# Pixracer_V1_FMU_Alternative_4.net
KiCad netlist of a schematic drawn in Altium Designer
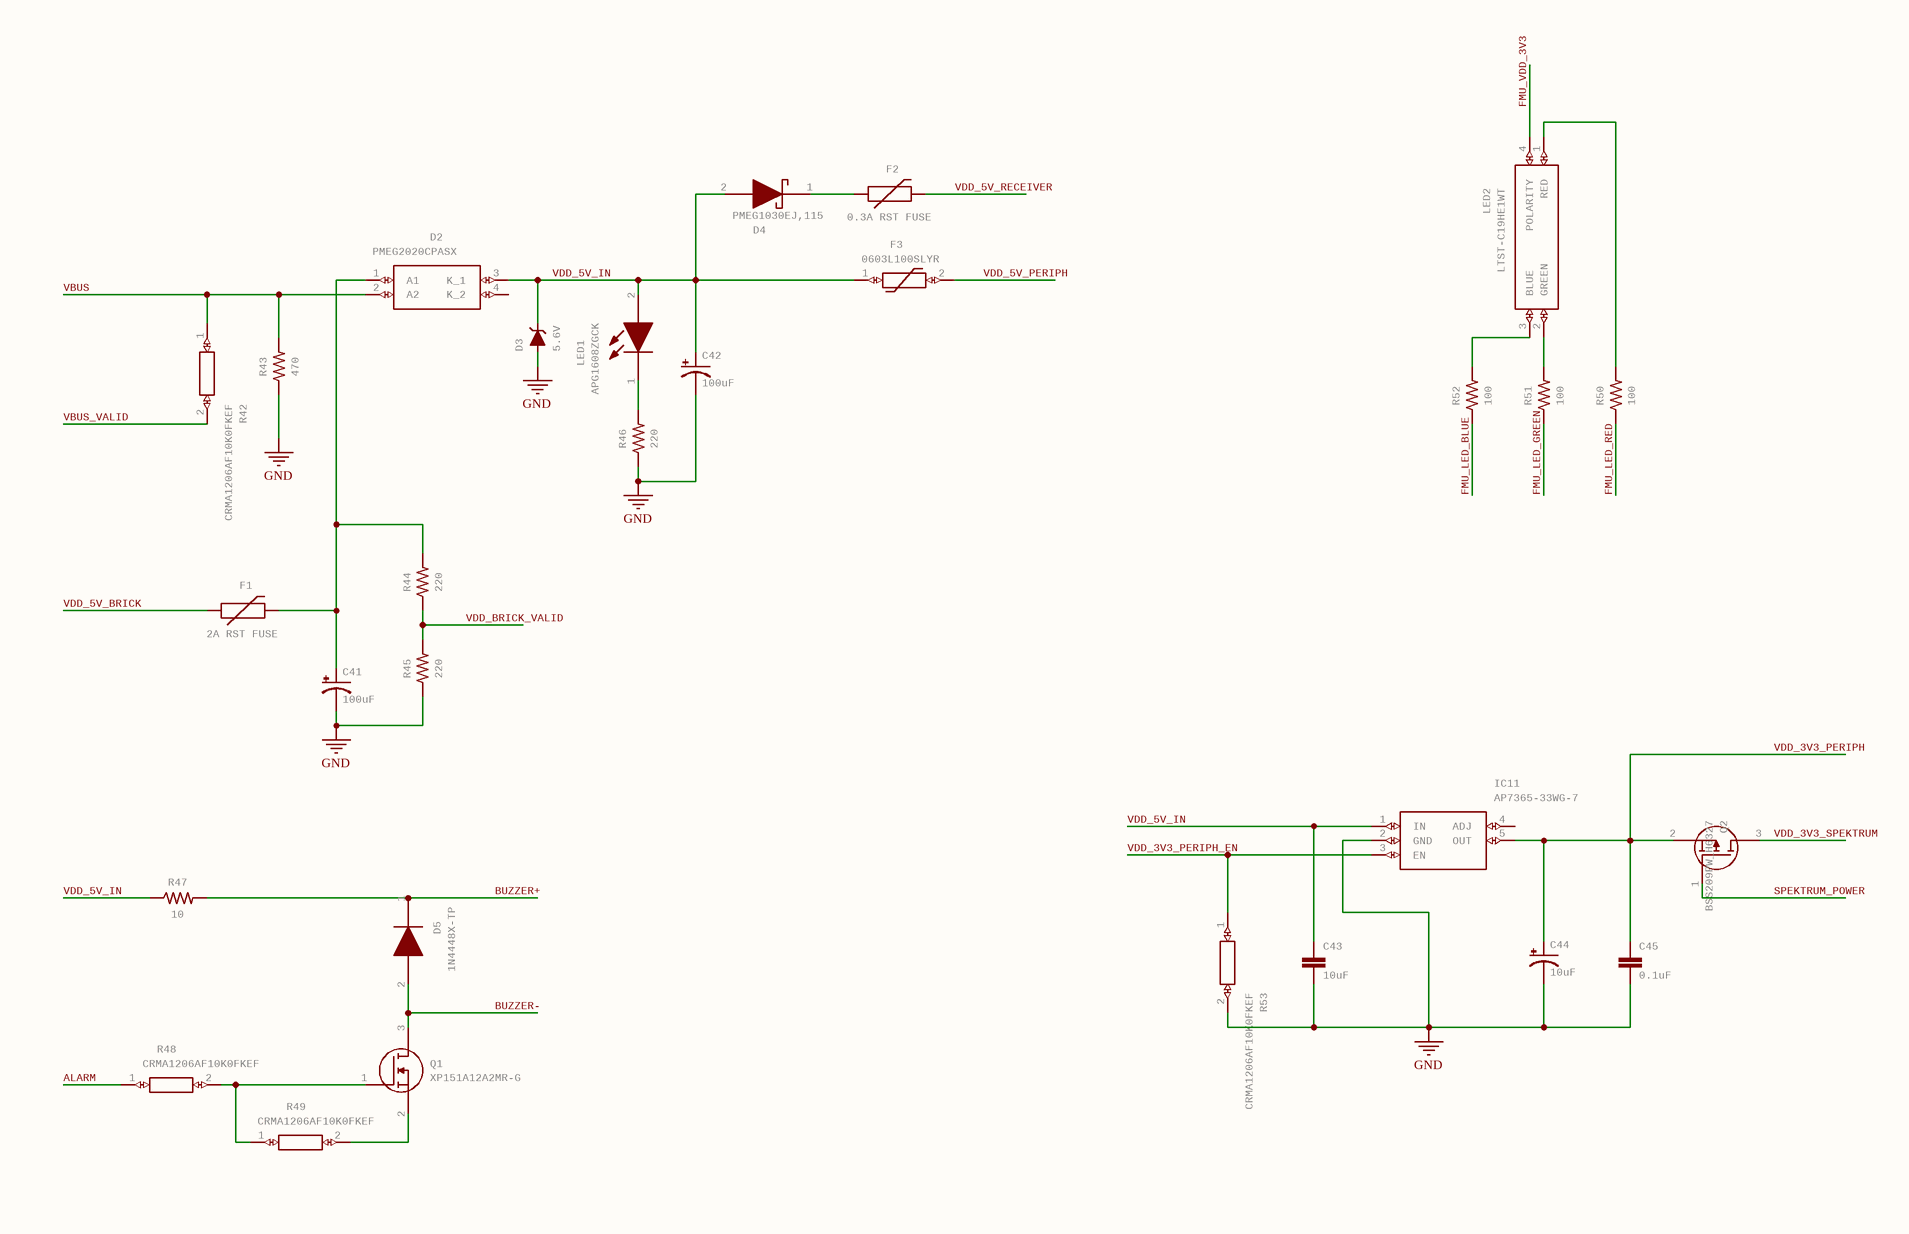
[diagram p0: Pixracer_V1_FMU_Alternative_4.SchDoc]

(export (version "E")
  (design (tool "Eeschema 10.0.6"))
  (components
    (comp (ref "C41")
      (value "100uF")
      (footprint "1206-POLAR")
      (libsource (lib "SparkFun-Capacitors") (part "100UF-POLAR-1206-6.3V-20%(TANT)"))
    )
    (comp (ref "C42")
      (value "100uF")
      (footprint "1206-POLAR")
      (libsource (lib "SparkFun-Capacitors") (part "100UF-POLAR-1206-6.3V-20%(TANT)"))
    )
    (comp (ref "C43")
      (value "10uF")
      (footprint "1206")
      (libsource (lib "SparkFun-Capacitors") (part "10UF-1206-6.3V-20%"))
    )
    (comp (ref "C44")
      (value "10uF")
      (footprint "0603-POLAR")
      (libsource (lib "SparkFun-Capacitors") (part "10UF-POLAR-0603-6.3V-20%(TANT)"))
    )
    (comp (ref "C45")
      (value "0.1uF")
      (footprint "0603")
      (libsource (lib "SparkFun-Capacitors") (part "0.1UF-0603-100V-10%-X7R-WE"))
    )
    (comp (ref "D2")
      (value "PMEG2020CPASX")
      (footprint "PMEG2020CPASX")
      (description "Schottky Diodes & Rectifiers 20V 2A dual MEGA Schottky")
      (fields (field (name "MOUSER_PART_NUMBER") "771-PMEG2020CPASX"))
      (libsource (lib "SamacSys_Parts") (part "PMEG2020CPASX"))
    )
    (comp (ref "D3")
      (value "5.6V")
      (footprint "SOT23-3")
      (libsource (lib "SparkFun-DiscreteSemi") (part "DIODE-ZENER-MMBZ5233BLT1G"))
    )
    (comp (ref "D4")
      (value "PMEG1030EJ,115")
      (footprint "SODFL2512X80N")
      (description "Schottky Diodes & Rectifiers SCHOTTKY 10V 3A")
      (fields (field (name "MOUSER_PART_NUMBER") "771-PMEG1030EJ-T/R"))
      (libsource (lib "SamacSys_Parts") (part "PMEG1030EJ,115"))
    )
    (comp (ref "D5")
      (value "1N4448X-TP")
      (footprint "1N4448XTP")
      (description "Diodes - General Purpose, Power, Switching 250mA 75V 500mA 250mA 150mW 75Vbr")
      (fields (field (name "MOUSER_PART_NUMBER") "833-1N4448X-TP"))
      (libsource (lib "SamacSys_Parts") (part "1N4448X-TP"))
    )
    (comp (ref "F1")
      (value "2A RST FUSE")
      (footprint "1206")
      (libsource (lib "SparkFun-Fuses") (part "PPTC_6V500MA-2"))
    )
    (comp (ref "F2")
      (value "0.3A RST FUSE")
      (footprint "0805")
      (libsource (lib "SparkFun-Fuses") (part "PPTC_6V500MA"))
    )
    (comp (ref "F3")
      (value "0603L100SLYR")
      (footprint "0603L050SLYR")
      (description "PTC 6V POLYFUSE SURF MOUNT 0603 SL 1.00A")
      (fields (field (name "MOUSER_PART_NUMBER") "576-0603L100SLYR"))
      (libsource (lib "SamacSys_Parts") (part "0603L100SLYR"))
    )
    (comp (ref "IC11")
      (value "AP7365-33WG-7")
      (footprint "SOT95P285X130-5N")
      (description "DiodesZetex AP7365-33WG-7, LDO Voltage Regulator, 600mA, 3.3 V +/-2%, 2  6 Vin, 5-Pin SOT-25")
      (fields (field (name "MOUSER_PART_NUMBER") "621-AP7365-33WG-7"))
      (libsource (lib "SamacSys_Parts") (part "AP7365-33WG-7"))
    )
    (comp (ref "LED1")
      (value "APG1608ZGCK")
      (footprint "LEDC1608X28N")
      (description "Standard LEDs - SMD 1.6X0.8MM")
      (fields (field (name "MOUSER_PART_NUMBER") "604-APG1608ZGCK"))
      (libsource (lib "SamacSys_Parts") (part "APG1608ZGCK"))
    )
    (comp (ref "LED2")
      (value "LTST-C19HE1WT")
      (footprint "LTST-C19HE1WT")
      (fields (field (name "MOUSER_PART_NUMBER") "859-LTST-C19HE1WT"))
      (libsource (lib "SamacSys_Parts") (part "LTST-C19HE1WT"))
    )
    (comp (ref "Q1")
      (value "XP151A12A2MR-G")
      (footprint "SOT95P280X130-3N")
      (description "Power MOSFET")
      (fields (field (name "MOUSER_PART_NUMBER") "865-XP151A12A2MR-G"))
      (libsource (lib "SamacSys_Parts") (part "XP151A12A2MR-G"))
    )
    (comp (ref "Q2")
      (value "BSS209PW_H6327")
      (footprint "SOT65P210X100-3N")
      (description "MOSFET P-Ch -20V -630mA SOT-323-3")
      (fields (field (name "MANUFACTURER_PART_NUMBER") "BSS209PW H6327"))
      (libsource (lib "SamacSys_Parts") (part "BSS209PW_H6327"))
    )
    (comp (ref "R42")
      (value "CRMA1206AF10K0FKEF")
      (footprint "RESC3216X74N")
      (description "Thick Film Resistors - SMD 0.30W 10Kohm 1% AEC-Q200")
      (fields (field (name "MOUSER_PART_NUMBER") "71-CRMA1206AF10K0FKF"))
      (libsource (lib "SamacSys_Parts") (part "CRMA1206AF10K0FKEF"))
    )
    (comp (ref "R43")
      (value "470")
      (footprint "0603")
      (libsource (lib "SparkFun-Resistors") (part "470OHM-0603-1/10W-1%"))
    )
    (comp (ref "R44")
      (value "220")
      (footprint "0603")
      (libsource (lib "SparkFun-Resistors") (part "220OHM-0603-1/10W-1%"))
    )
    (comp (ref "R45")
      (value "220")
      (footprint "0603")
      (libsource (lib "SparkFun-Resistors") (part "220OHM-0603-1/10W-1%"))
    )
    (comp (ref "R46")
      (value "220")
      (footprint "0603")
      (libsource (lib "SparkFun-Resistors") (part "220OHM-0603-1/10W-1%"))
    )
    (comp (ref "R47")
      (value "10")
      (footprint "0603")
      (libsource (lib "SparkFun-Resistors") (part "10OHM-0603-1/10W-5%"))
    )
    (comp (ref "R48")
      (value "CRMA1206AF10K0FKEF")
      (footprint "RESC3216X74N")
      (description "Thick Film Resistors - SMD 0.30W 10Kohm 1% AEC-Q200")
      (fields (field (name "MOUSER_PART_NUMBER") "71-CRMA1206AF10K0FKF"))
      (libsource (lib "SamacSys_Parts") (part "CRMA1206AF10K0FKEF"))
    )
    (comp (ref "R49")
      (value "CRMA1206AF10K0FKEF")
      (footprint "RESC3216X74N")
      (description "Thick Film Resistors - SMD 0.30W 10Kohm 1% AEC-Q200")
      (fields (field (name "MOUSER_PART_NUMBER") "71-CRMA1206AF10K0FKF"))
      (libsource (lib "SamacSys_Parts") (part "CRMA1206AF10K0FKEF"))
    )
    (comp (ref "R50")
      (value "100")
      (footprint "0603")
      (libsource (lib "SparkFun-Resistors") (part "100OHM-0603-1/10W-1%"))
    )
    (comp (ref "R51")
      (value "100")
      (footprint "0603")
      (libsource (lib "SparkFun-Resistors") (part "100OHM-0603-1/10W-1%"))
    )
    (comp (ref "R52")
      (value "100")
      (footprint "0603")
      (libsource (lib "SparkFun-Resistors") (part "100OHM-0603-1/10W-1%"))
    )
    (comp (ref "R53")
      (value "CRMA1206AF10K0FKEF")
      (footprint "RESC3216X74N")
      (description "Thick Film Resistors - SMD 0.30W 10Kohm 1% AEC-Q200")
      (fields (field (name "MOUSER_PART_NUMBER") "71-CRMA1206AF10K0FKF"))
      (libsource (lib "SamacSys_Parts") (part "CRMA1206AF10K0FKEF"))
    )
  )
  (nets
    (net (code "1") (name "/ALARM") (class "Default")
      (node (ref "R48") (pin "1") (pinfunction "1_1") (pintype "bidirectional"))
    )
    (net (code "2") (name "/BUZZER+") (class "Default")
      (node (ref "D5") (pin "1") (pinfunction "K_1") (pintype "bidirectional"))
      (node (ref "R47") (pin "2") (pinfunction "2_2") (pintype "passive"))
    )
    (net (code "3") (name "/BUZZER-") (class "Default")
      (node (ref "D5") (pin "2") (pinfunction "A_2") (pintype "bidirectional"))
      (node (ref "Q1") (pin "3") (pinfunction "D_3") (pintype "bidirectional"))
    )
    (net (code "4") (name "/FMU_LED_BLUE") (class "Default")
      (node (ref "R52") (pin "1") (pinfunction "1_1") (pintype "passive"))
    )
    (net (code "5") (name "/FMU_LED_GREEN") (class "Default")
      (node (ref "R51") (pin "1") (pinfunction "1_1") (pintype "passive"))
    )
    (net (code "6") (name "/FMU_LED_RED") (class "Default")
      (node (ref "R50") (pin "1") (pinfunction "1_1") (pintype "passive"))
    )
    (net (code "7") (name "/FMU_VDD_3V3") (class "Default")
      (node (ref "LED2") (pin "4") (pinfunction "POLARITY_4") (pintype "bidirectional"))
    )
    (net (code "8") (name "/SPEKTRUM_POWER") (class "Default")
      (node (ref "Q2") (pin "1") (pinfunction "G_1") (pintype "bidirectional"))
    )
    (net (code "9") (name "/VBUS") (class "Default")
      (node (ref "D2") (pin "2") (pinfunction "A2_2") (pintype "bidirectional"))
      (node (ref "R42") (pin "1") (pinfunction "1_1") (pintype "bidirectional"))
      (node (ref "R43") (pin "2") (pinfunction "2_2") (pintype "passive"))
    )
    (net (code "10") (name "/VBUS_VALID") (class "Default")
      (node (ref "R42") (pin "2") (pinfunction "2_2") (pintype "bidirectional"))
    )
    (net (code "11") (name "/VDD_3V3_PERIPH") (class "Default")
      (node (ref "C44") (pin "+") (pinfunction "+_+") (pintype "passive"))
      (node (ref "C45") (pin "1") (pinfunction "1_1") (pintype "passive"))
      (node (ref "IC11") (pin "5") (pinfunction "OUT_5") (pintype "bidirectional"))
      (node (ref "Q2") (pin "2") (pinfunction "S_2") (pintype "bidirectional"))
    )
    (net (code "12") (name "/VDD_3V3_PERIPH_EN") (class "Default")
      (node (ref "IC11") (pin "3") (pinfunction "EN_3") (pintype "bidirectional"))
      (node (ref "R53") (pin "1") (pinfunction "1_1") (pintype "bidirectional"))
    )
    (net (code "13") (name "/VDD_3V3_SPEKTRUM") (class "Default")
      (node (ref "Q2") (pin "3") (pinfunction "D_3") (pintype "bidirectional"))
    )
    (net (code "14") (name "/VDD_5V_BRICK") (class "Default")
      (node (ref "F1") (pin "1") (pinfunction "1_1") (pintype "bidirectional"))
    )
    (net (code "15") (name "/VDD_5V_IN") (class "Default")
      (node (ref "C42") (pin "1") (pinfunction "+_1") (pintype "passive"))
      (node (ref "C43") (pin "1") (pinfunction "1_1") (pintype "passive"))
      (node (ref "D2") (pin "3") (pinfunction "K_1_3") (pintype "bidirectional"))
      (node (ref "D3") (pin "3") (pinfunction "C_3") (pintype "passive"))
      (node (ref "D4") (pin "2") (pinfunction "A_2") (pintype "bidirectional"))
      (node (ref "F3") (pin "1") (pinfunction "1_1") (pintype "bidirectional"))
      (node (ref "IC11") (pin "1") (pinfunction "IN_1") (pintype "bidirectional"))
      (node (ref "LED1") (pin "2") (pinfunction "A_2") (pintype "bidirectional"))
      (node (ref "R47") (pin "1") (pinfunction "1_1") (pintype "passive"))
    )
    (net (code "16") (name "/VDD_5V_PERIPH") (class "Default")
      (node (ref "F3") (pin "2") (pinfunction "2_2") (pintype "bidirectional"))
    )
    (net (code "17") (name "/VDD_5V_RECEIVER") (class "Default")
      (node (ref "F2") (pin "2") (pinfunction "2_2") (pintype "bidirectional"))
    )
    (net (code "18") (name "/VDD_BRICK_VALID") (class "Default")
      (node (ref "R44") (pin "1") (pinfunction "1_1") (pintype "passive"))
      (node (ref "R45") (pin "2") (pinfunction "2_2") (pintype "passive"))
    )
    (net (code "19") (name "GND") (class "Default")
      (node (ref "C41") (pin "2") (pinfunction "-_2") (pintype "passive"))
      (node (ref "C42") (pin "2") (pinfunction "-_2") (pintype "passive"))
      (node (ref "C43") (pin "2") (pinfunction "2_2") (pintype "passive"))
      (node (ref "C44") (pin "-") (pinfunction "-_-") (pintype "passive"))
      (node (ref "C45") (pin "2") (pinfunction "2_2") (pintype "passive"))
      (node (ref "D3") (pin "1") (pinfunction "A_1") (pintype "passive"))
      (node (ref "IC11") (pin "2") (pinfunction "GND_2") (pintype "bidirectional"))
      (node (ref "R43") (pin "1") (pinfunction "1_1") (pintype "passive"))
      (node (ref "R45") (pin "1") (pinfunction "1_1") (pintype "passive"))
      (node (ref "R46") (pin "1") (pinfunction "1_1") (pintype "passive"))
      (node (ref "R53") (pin "2") (pinfunction "2_2") (pintype "bidirectional"))
    )
    (net (code "20") (name "Net-(C41-+)") (class "Default")
      (node (ref "C41") (pin "1") (pinfunction "+_1") (pintype "passive"))
      (node (ref "D2") (pin "1") (pinfunction "A1_1") (pintype "bidirectional"))
      (node (ref "F1") (pin "2") (pinfunction "2_2") (pintype "bidirectional"))
      (node (ref "R44") (pin "2") (pinfunction "2_2") (pintype "passive"))
    )
    (net (code "21") (name "Net-(D4-K)") (class "Default")
      (node (ref "D4") (pin "1") (pinfunction "K_1") (pintype "bidirectional"))
      (node (ref "F2") (pin "1") (pinfunction "1_1") (pintype "bidirectional"))
    )
    (net (code "22") (name "Net-(LED1-K)") (class "Default")
      (node (ref "LED1") (pin "1") (pinfunction "K_1") (pintype "bidirectional"))
      (node (ref "R46") (pin "2") (pinfunction "2_2") (pintype "passive"))
    )
    (net (code "23") (name "Net-(LED2-BLUE)") (class "Default")
      (node (ref "LED2") (pin "3") (pinfunction "BLUE_3") (pintype "bidirectional"))
      (node (ref "R52") (pin "2") (pinfunction "2_2") (pintype "passive"))
    )
    (net (code "24") (name "Net-(LED2-GREEN)") (class "Default")
      (node (ref "LED2") (pin "2") (pinfunction "GREEN_2") (pintype "bidirectional"))
      (node (ref "R51") (pin "2") (pinfunction "2_2") (pintype "passive"))
    )
    (net (code "25") (name "Net-(LED2-RED)") (class "Default")
      (node (ref "LED2") (pin "1") (pinfunction "RED_1") (pintype "bidirectional"))
      (node (ref "R50") (pin "2") (pinfunction "2_2") (pintype "passive"))
    )
    (net (code "26") (name "Net-(Q1-G)") (class "Default")
      (node (ref "Q1") (pin "1") (pinfunction "G_1") (pintype "bidirectional"))
      (node (ref "R48") (pin "2") (pinfunction "2_2") (pintype "bidirectional"))
      (node (ref "R49") (pin "1") (pinfunction "1_1") (pintype "bidirectional"))
    )
    (net (code "27") (name "Net-(Q1-S)") (class "Default")
      (node (ref "Q1") (pin "2") (pinfunction "S_2") (pintype "bidirectional"))
      (node (ref "R49") (pin "2") (pinfunction "2_2") (pintype "bidirectional"))
    )
    (net (code "28") (name "unconnected-(D2-K_2-Pad4)") (class "Default")
      (node (ref "D2") (pin "4") (pinfunction "K_2_4") (pintype "bidirectional"))
    )
    (net (code "29") (name "unconnected-(IC11-ADJ-Pad4)") (class "Default")
      (node (ref "IC11") (pin "4") (pinfunction "ADJ_4") (pintype "bidirectional"))
    )
  )
)
